# User-Control.net
KiCad netlist of a schematic drawn in Altium Designer
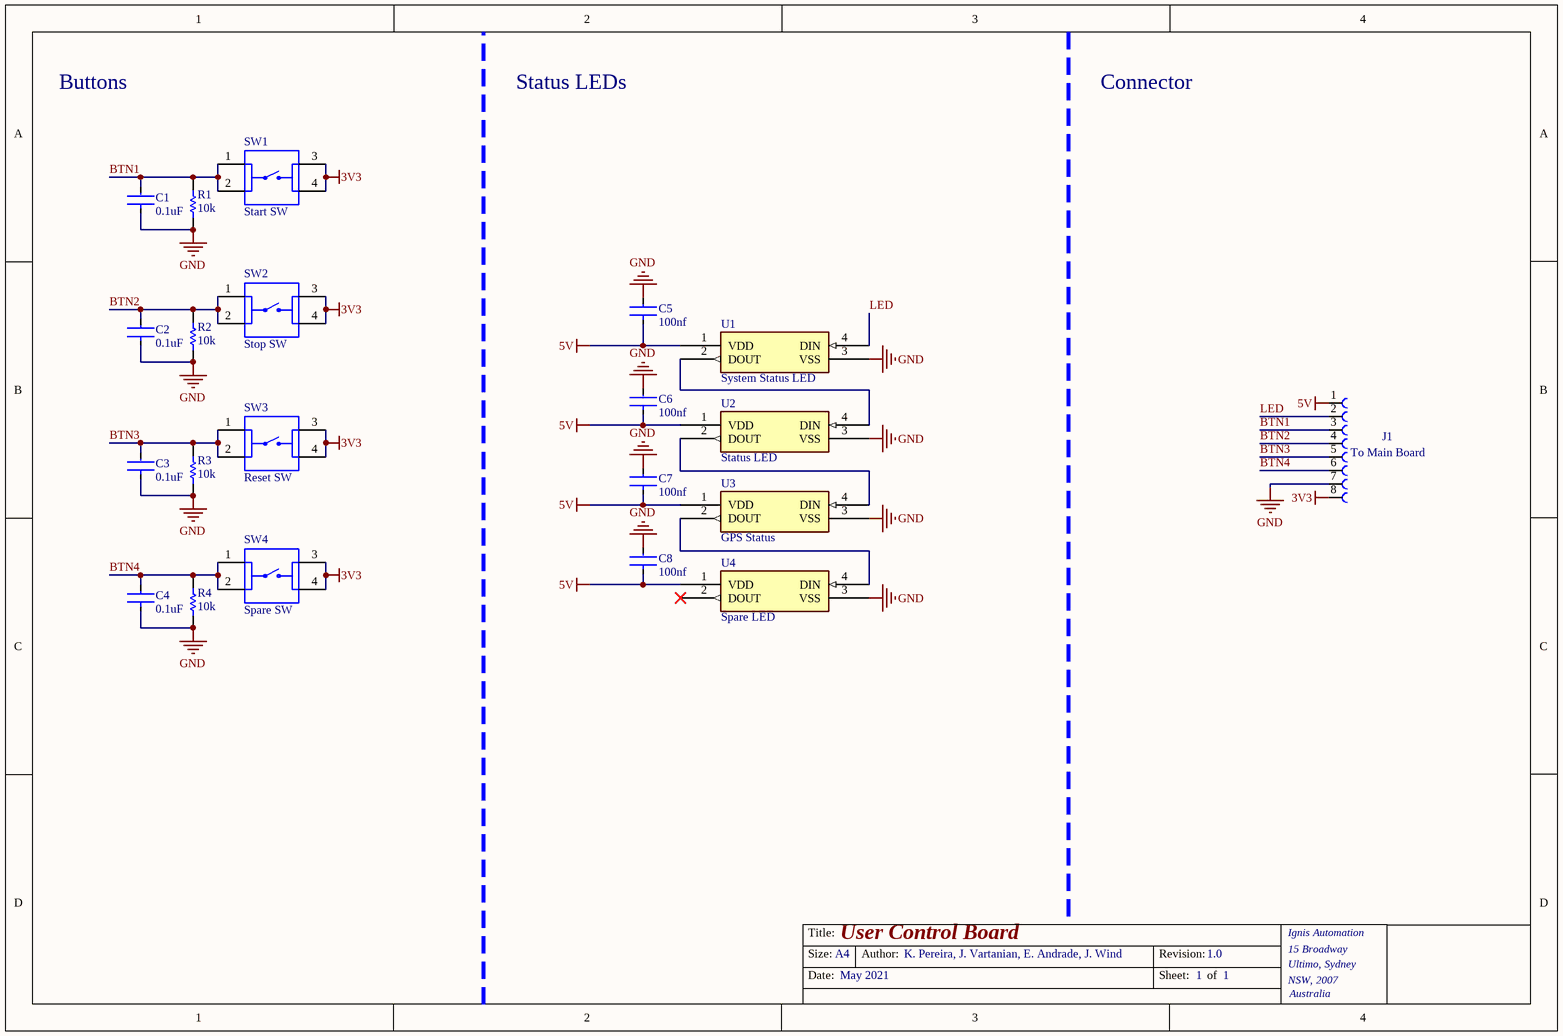
[diagram p0: User-Control.SchDoc]

(export (version "E")
  (design (tool "Eeschema 10.0.6"))
  (components
    (comp (ref "C1")
      (value "0.1uF")
      (footprint "FP-CL10-IPC_C")
      (description "CAP CER 0.1UF 50V X7R 0603")
      (fields (field (name "PART NUMBER") "1276-CL10B104KB8NNNLCT-ND"))
      (libsource (lib "Altium Content Vault") (part "b4654b650e69147ec39a6b967a45e02"))
    )
    (comp (ref "C2")
      (value "0.1uF")
      (footprint "FP-CL10-IPC_C")
      (description "CAP CER 0.1UF 50V X7R 0603")
      (fields (field (name "PART NUMBER") "1276-CL10B104KB8NNNLCT-ND"))
      (libsource (lib "Altium Content Vault") (part "b4654b650e69147ec39a6b967a45e02"))
    )
    (comp (ref "C3")
      (value "0.1uF")
      (footprint "FP-CL10-IPC_C")
      (description "CAP CER 0.1UF 50V X7R 0603")
      (fields (field (name "PART NUMBER") "1276-CL10B104KB8NNNLCT-ND"))
      (libsource (lib "Altium Content Vault") (part "b4654b650e69147ec39a6b967a45e02"))
    )
    (comp (ref "C4")
      (value "0.1uF")
      (footprint "FP-CL10-IPC_C")
      (description "CAP CER 0.1UF 50V X7R 0603")
      (fields (field (name "PART NUMBER") "1276-CL10B104KB8NNNLCT-ND"))
      (libsource (lib "Altium Content Vault") (part "b4654b650e69147ec39a6b967a45e02"))
    )
    (comp (ref "C5")
      (value "100nf")
      (footprint "FP-CL10-IPC_C")
      (description "CAP CER 0.1UF 50V X7R 0603")
      (fields (field (name "PART NUMBER") "1276-CL10B104KB8NNNLCT-ND"))
      (libsource (lib "Altium Content Vault") (part "b4654b650e69147ec39a6b967a45e02"))
    )
    (comp (ref "C6")
      (value "100nf")
      (footprint "FP-CL10-IPC_C")
      (description "CAP CER 0.1UF 50V X7R 0603")
      (fields (field (name "PART NUMBER") "1276-CL10B104KB8NNNLCT-ND"))
      (libsource (lib "Altium Content Vault") (part "b4654b650e69147ec39a6b967a45e02"))
    )
    (comp (ref "C7")
      (value "100nf")
      (footprint "FP-CL10-IPC_C")
      (description "CAP CER 0.1UF 50V X7R 0603")
      (fields (field (name "PART NUMBER") "1276-CL10B104KB8NNNLCT-ND"))
      (libsource (lib "Altium Content Vault") (part "b4654b650e69147ec39a6b967a45e02"))
    )
    (comp (ref "C8")
      (value "100nf")
      (footprint "FP-CL10-IPC_C")
      (description "CAP CER 0.1UF 50V X7R 0603")
      (fields (field (name "PART NUMBER") "1276-CL10B104KB8NNNLCT-ND"))
      (libsource (lib "Altium Content Vault") (part "b4654b650e69147ec39a6b967a45e02"))
    )
    (comp (ref "J1")
      (value "To Main Board")
      (footprint "8pin:61300711821")
      (fields (field (name "MF") "WÃ¼rth Elektronik") (field (name "MP") "61300711821"))
      (libsource (lib "8pin") (part "61300711821"))
    )
    (comp (ref "R1")
      (value "10k")
      (footprint "RESC1608X55X30NL15T15")
      (description "RES SMD 10K OHM 1% 1/10W 0603")
      (fields (field (name "PART NUMBER") "A121523CT-ND"))
      (libsource (lib "Altium Content Vault") (part "RES"))
    )
    (comp (ref "R2")
      (value "10k")
      (footprint "RESC1608X55X30NL15T15")
      (description "RES SMD 10K OHM 1% 1/10W 0603")
      (fields (field (name "PART NUMBER") "A121523CT-ND"))
      (libsource (lib "Altium Content Vault") (part "RES"))
    )
    (comp (ref "R3")
      (value "10k")
      (footprint "RESC1608X55X30NL15T15")
      (description "RES SMD 10K OHM 1% 1/10W 0603")
      (fields (field (name "PART NUMBER") "A121523CT-ND"))
      (libsource (lib "Altium Content Vault") (part "RES"))
    )
    (comp (ref "R4")
      (value "10k")
      (footprint "RESC1608X55X30NL15T15")
      (description "RES SMD 10K OHM 1% 1/10W 0603")
      (fields (field (name "PART NUMBER") "A121523CT-ND"))
      (libsource (lib "Altium Content Vault") (part "RES"))
    )
    (comp (ref "SW1")
      (value "Start SW")
      (footprint "1825910-6:SW_1825910-6-4")
      (description "SWITCH TACTILE SPST-NO 0.05A 24V")
      (fields (field (name "PART NUMBER") "450-1650-ND"))
      (libsource (lib "1825910-6") (part "1825910-6"))
    )
    (comp (ref "SW2")
      (value "Stop SW")
      (footprint "1825910-6:SW_1825910-6-4")
      (description "SWITCH TACTILE SPST-NO 0.05A 24V")
      (fields (field (name "PART NUMBER") "450-1650-ND"))
      (libsource (lib "1825910-6") (part "1825910-6"))
    )
    (comp (ref "SW3")
      (value "Reset SW")
      (footprint "1825910-6:SW_1825910-6-4")
      (description "SWITCH TACTILE SPST-NO 0.05A 24V")
      (fields (field (name "PART NUMBER") "450-1650-ND"))
      (libsource (lib "1825910-6") (part "1825910-6"))
    )
    (comp (ref "SW4")
      (value "Spare SW")
      (footprint "1825910-6:SW_1825910-6-4")
      (description "SWITCH TACTILE SPST-NO 0.05A 24V")
      (fields (field (name "PART NUMBER") "450-1650-ND"))
      (libsource (lib "1825910-6") (part "1825910-6"))
    )
    (comp (ref "U1")
      (value "System Status LED")
      (footprint "WS2812B:WS2812B_WDS")
      (description "WS2812B")
      (libsource (lib "WS2812B") (part "WS2812B"))
    )
    (comp (ref "U2")
      (value "Status LED")
      (footprint "WS2812B:WS2812B_WDS")
      (description "WS2812B")
      (libsource (lib "WS2812B") (part "WS2812B"))
    )
    (comp (ref "U3")
      (value "GPS Status")
      (footprint "WS2812B:WS2812B_WDS")
      (description "WS2812B")
      (libsource (lib "WS2812B") (part "WS2812B"))
    )
    (comp (ref "U4")
      (value "Spare LED")
      (footprint "WS2812B:WS2812B_WDS")
      (description "WS2812B")
      (libsource (lib "WS2812B") (part "WS2812B"))
    )
  )
  (nets
    (net (code "1") (name "/BTN1") (class "Default")
      (node (ref "C1") (pin "2") (pinfunction "2_2") (pintype "passive"))
      (node (ref "J1") (pin "3") (pinfunction "3_3") (pintype "passive"))
      (node (ref "R1") (pin "2") (pinfunction "2_2") (pintype "passive"))
      (node (ref "SW1") (pin "1") (pinfunction "1_1") (pintype "passive"))
      (node (ref "SW1") (pin "2") (pinfunction "2_2") (pintype "passive"))
    )
    (net (code "2") (name "/BTN2") (class "Default")
      (node (ref "C2") (pin "2") (pinfunction "2_2") (pintype "passive"))
      (node (ref "J1") (pin "4") (pinfunction "4_4") (pintype "passive"))
      (node (ref "R2") (pin "2") (pinfunction "2_2") (pintype "passive"))
      (node (ref "SW2") (pin "1") (pinfunction "1_1") (pintype "passive"))
      (node (ref "SW2") (pin "2") (pinfunction "2_2") (pintype "passive"))
    )
    (net (code "3") (name "/BTN3") (class "Default")
      (node (ref "C3") (pin "2") (pinfunction "2_2") (pintype "passive"))
      (node (ref "J1") (pin "5") (pinfunction "5_5") (pintype "passive"))
      (node (ref "R3") (pin "2") (pinfunction "2_2") (pintype "passive"))
      (node (ref "SW3") (pin "1") (pinfunction "1_1") (pintype "passive"))
      (node (ref "SW3") (pin "2") (pinfunction "2_2") (pintype "passive"))
    )
    (net (code "4") (name "/BTN4") (class "Default")
      (node (ref "C4") (pin "2") (pinfunction "2_2") (pintype "passive"))
      (node (ref "J1") (pin "6") (pinfunction "6_6") (pintype "passive"))
      (node (ref "R4") (pin "2") (pinfunction "2_2") (pintype "passive"))
      (node (ref "SW4") (pin "1") (pinfunction "1_1") (pintype "passive"))
      (node (ref "SW4") (pin "2") (pinfunction "2_2") (pintype "passive"))
    )
    (net (code "5") (name "/LED") (class "Default")
      (node (ref "J1") (pin "2") (pinfunction "2_2") (pintype "passive"))
      (node (ref "U1") (pin "4") (pinfunction "DIN_4") (pintype "input"))
    )
    (net (code "6") (name "3V3") (class "Default")
      (node (ref "J1") (pin "8") (pinfunction "8_8") (pintype "passive"))
      (node (ref "SW1") (pin "3") (pinfunction "3_3") (pintype "passive"))
      (node (ref "SW1") (pin "4") (pinfunction "4_4") (pintype "passive"))
      (node (ref "SW2") (pin "3") (pinfunction "3_3") (pintype "passive"))
      (node (ref "SW2") (pin "4") (pinfunction "4_4") (pintype "passive"))
      (node (ref "SW3") (pin "3") (pinfunction "3_3") (pintype "passive"))
      (node (ref "SW3") (pin "4") (pinfunction "4_4") (pintype "passive"))
      (node (ref "SW4") (pin "3") (pinfunction "3_3") (pintype "passive"))
      (node (ref "SW4") (pin "4") (pinfunction "4_4") (pintype "passive"))
    )
    (net (code "7") (name "5V") (class "Default")
      (node (ref "C5") (pin "1") (pinfunction "1_1") (pintype "passive"))
      (node (ref "C6") (pin "1") (pinfunction "1_1") (pintype "passive"))
      (node (ref "C7") (pin "1") (pinfunction "1_1") (pintype "passive"))
      (node (ref "C8") (pin "1") (pinfunction "1_1") (pintype "passive"))
      (node (ref "J1") (pin "1") (pinfunction "1_1") (pintype "passive"))
      (node (ref "U1") (pin "1") (pinfunction "VDD_1") (pintype "power_in"))
      (node (ref "U2") (pin "1") (pinfunction "VDD_1") (pintype "power_in"))
      (node (ref "U3") (pin "1") (pinfunction "VDD_1") (pintype "power_in"))
      (node (ref "U4") (pin "1") (pinfunction "VDD_1") (pintype "power_in"))
    )
    (net (code "8") (name "GND") (class "Default")
      (node (ref "C1") (pin "1") (pinfunction "1_1") (pintype "passive"))
      (node (ref "C2") (pin "1") (pinfunction "1_1") (pintype "passive"))
      (node (ref "C3") (pin "1") (pinfunction "1_1") (pintype "passive"))
      (node (ref "C4") (pin "1") (pinfunction "1_1") (pintype "passive"))
      (node (ref "C5") (pin "2") (pinfunction "2_2") (pintype "passive"))
      (node (ref "C6") (pin "2") (pinfunction "2_2") (pintype "passive"))
      (node (ref "C7") (pin "2") (pinfunction "2_2") (pintype "passive"))
      (node (ref "C8") (pin "2") (pinfunction "2_2") (pintype "passive"))
      (node (ref "J1") (pin "7") (pinfunction "7_7") (pintype "passive"))
      (node (ref "R1") (pin "1") (pinfunction "1_1") (pintype "passive"))
      (node (ref "R2") (pin "1") (pinfunction "1_1") (pintype "passive"))
      (node (ref "R3") (pin "1") (pinfunction "1_1") (pintype "passive"))
      (node (ref "R4") (pin "1") (pinfunction "1_1") (pintype "passive"))
      (node (ref "U1") (pin "3") (pinfunction "VSS_3") (pintype "passive"))
      (node (ref "U2") (pin "3") (pinfunction "VSS_3") (pintype "passive"))
      (node (ref "U3") (pin "3") (pinfunction "VSS_3") (pintype "passive"))
      (node (ref "U4") (pin "3") (pinfunction "VSS_3") (pintype "passive"))
    )
    (net (code "9") (name "Net-(U1-DOUT)") (class "Default")
      (node (ref "U1") (pin "2") (pinfunction "DOUT_2") (pintype "output"))
      (node (ref "U2") (pin "4") (pinfunction "DIN_4") (pintype "input"))
    )
    (net (code "10") (name "Net-(U2-DOUT)") (class "Default")
      (node (ref "U2") (pin "2") (pinfunction "DOUT_2") (pintype "output"))
      (node (ref "U3") (pin "4") (pinfunction "DIN_4") (pintype "input"))
    )
    (net (code "11") (name "Net-(U3-DOUT)") (class "Default")
      (node (ref "U3") (pin "2") (pinfunction "DOUT_2") (pintype "output"))
      (node (ref "U4") (pin "4") (pinfunction "DIN_4") (pintype "input"))
    )
    (net (code "12") (name "unconnected-(U4-DOUT-Pad2)") (class "Default")
      (node (ref "U4") (pin "2") (pinfunction "DOUT_2") (pintype "output+no_connect"))
    )
  )
)
